# nrf_ha_sensor_Power_supply.net
KiCad netlist of a schematic drawn in Altium Designer
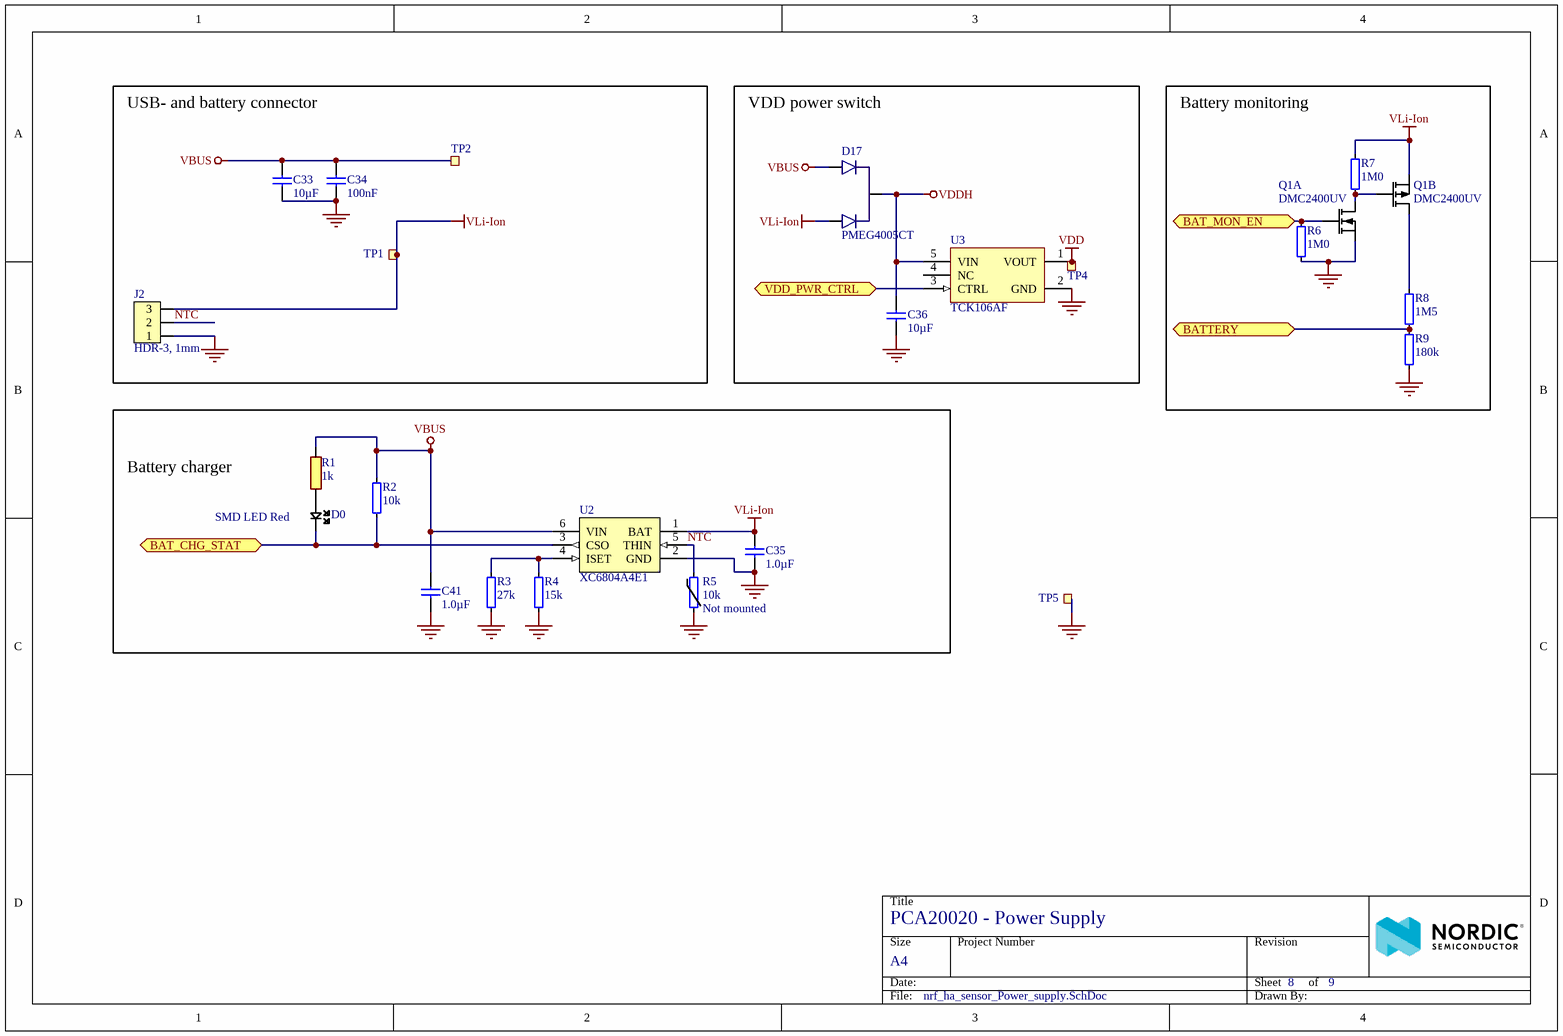
[diagram p0: nrf_ha_sensor_Power_supply.SchDoc]

(export (version "E")
  (design (tool "Eeschema 10.0.6"))
  (components
    (comp (ref "C33")
      (value "10µF")
      (footprint "CAPC1608X06L")
      (description "Capacitor, X5R, ±20%")
      (fields (field (name "PART NUMBER") "C0603-10µ") (field (name "PUBLISHER") "Nordic Semiconductor"))
      (libsource (lib "Nordic Passive DB") (part "CAP"))
    )
    (comp (ref "C34")
      (value "100nF")
      (footprint "CAPC1005X04L")
      (description "Capacitor, X7R, ±10%")
      (fields (field (name "PART NUMBER") "C0402-100n") (field (name "PUBLISHER") "Nordic Semiconductor"))
      (libsource (lib "Nordic Passive DB") (part "CAP"))
    )
    (comp (ref "C35")
      (value "1.0µF")
      (footprint "CAPC1608X06L")
      (description "Capacitor, X7R, ±10%")
      (fields (field (name "PART NUMBER") "C0603-1µ0") (field (name "PUBLISHER") "Nordic Semiconductor"))
      (libsource (lib "Nordic Passive DB") (part "CAP"))
    )
    (comp (ref "C36")
      (value "10µF")
      (footprint "CAPC1608X06L")
      (description "Capacitor, X5R, ±20%")
      (fields (field (name "PART NUMBER") "C0603-10µ") (field (name "PUBLISHER") "Nordic Semiconductor"))
      (libsource (lib "Nordic Passive DB") (part "CAP"))
    )
    (comp (ref "C41")
      (value "1.0µF")
      (footprint "CAPC1608X06L")
      (description "Capacitor, X7R, ±10%")
      (fields (field (name "PART NUMBER") "C0603-1µ0") (field (name "PUBLISHER") "Nordic Semiconductor"))
      (libsource (lib "Nordic Passive DB") (part "CAP"))
    )
    (comp (ref "D0")
      (value "SMD LED Red")
      (footprint "I_LEDC0603(1608)_N")
      (description "SMD")
      (libsource (lib "OVLib_64") (part "LED"))
    )
    (comp (ref "D17")
      (value "PMEG4005CT")
      (footprint "SOT95P230X110-3N")
      (libsource (lib "PMEG4005CT") (part "PMEG4005CT"))
    )
    (comp (ref "J2")
      (value "HDR-3, 1mm")
      (footprint "SM03B-SRSS-TB")
      (description "1.0mm pitch connector side entry SMD")
      (fields
        (field (name "PART NUMBER") "SM03B-SRSS-TB")
        (field (name "MANUFACTURER") "JST")
        (field (name "PUBLISHER") "Nordic Semiconductor")
      )
      (libsource (lib "Nordic Passive DB") (part "CONN-3"))
    )
    (comp (ref "Q1")
      (value "DMC2400UV")
      (footprint "SOTFL50P162X60-6N")
      (description "Dual N & P Ch MOFET, 1.03A/0.7A, 480mOhm, 450mW")
      (fields
        (field (name "MANUFACTURER") "Diodes Incorporated")
        (field (name "PUBLISHER") "Nordic Semiconductor")
      )
      (libsource (lib "Nordic Discrete DB") (part "T{colon}FET-N/P-DUAL"))
    )
    (comp (ref "R1")
      (value "1k")
      (footprint "RESC0603(1608)_N")
      (description "0.1W 1% Thick film resistor")
      (libsource (lib "OVLib_64") (part "Resistor2"))
    )
    (comp (ref "R2")
      (value "10k")
      (footprint "RESC1005X04L")
      (description "Resistor, ±1%, 0.063W")
      (fields (field (name "PART NUMBER") "R0402-10k") (field (name "PUBLISHER") "Nordic Semiconductor"))
      (libsource (lib "Nordic Passive DB") (part "RES_1"))
    )
    (comp (ref "R3")
      (value "27k")
      (footprint "RESC1005X04L")
      (description "Resistor, ±1%, 0.063W")
      (fields (field (name "PART NUMBER") "R0402-27k") (field (name "PUBLISHER") "Nordic Semiconductor"))
      (libsource (lib "Nordic Passive DB") (part "RES_1"))
    )
    (comp (ref "R4")
      (value "15k")
      (footprint "RESC1005X04L")
      (description "Resistor, ±1%, 0.063W")
      (fields (field (name "PART NUMBER") "R0402-15k") (field (name "PUBLISHER") "Nordic Semiconductor"))
      (libsource (lib "Nordic Passive DB") (part "RES_1"))
    )
    (comp (ref "R5")
      (value "10k")
      (footprint "RESC1005X04L")
      (description "THERMISTOR 10K OHM NTC 0402 SMD")
      (fields
        (field (name "PART NUMBER") "NCP15XH103F03RC")
        (field (name "MANUFACTURER") "Murata")
        (field (name "ASSEMBLY") "Not mounted")
        (field (name "PUBLISHER") "Nordic Semiconductor")
      )
      (libsource (lib "Nordic Passive DB") (part "RES_NTC"))
    )
    (comp (ref "R6")
      (value "1M0")
      (footprint "RESC1005X04L")
      (description "Resistor, ±1%, 0.063W")
      (fields (field (name "PART NUMBER") "R0402-1M0") (field (name "PUBLISHER") "Nordic Semiconductor"))
      (libsource (lib "Nordic Passive DB") (part "RES_1"))
    )
    (comp (ref "R7")
      (value "1M0")
      (footprint "RESC1005X04L")
      (description "Resistor, ±1%, 0.063W")
      (fields (field (name "PART NUMBER") "R0402-1M0") (field (name "PUBLISHER") "Nordic Semiconductor"))
      (libsource (lib "Nordic Passive DB") (part "RES_1"))
    )
    (comp (ref "R8")
      (value "1M5")
      (footprint "RESC1005X04L")
      (description "Resistor, ±1%, 0.063W")
      (fields (field (name "PART NUMBER") "R0402-1M5") (field (name "PUBLISHER") "Nordic Semiconductor"))
      (libsource (lib "Nordic Passive DB") (part "RES_1"))
    )
    (comp (ref "R9")
      (value "180k")
      (footprint "RESC1005X04L")
      (description "Resistor, ±1%, 0.063W")
      (fields (field (name "PART NUMBER") "R0402-180k") (field (name "PUBLISHER") "Nordic Semiconductor"))
      (libsource (lib "Nordic Passive DB") (part "RES_1"))
    )
    (comp (ref "TP1")
      (value "Ø1.5mm,SMD")
      (footprint "TP_SMD_Ø1.5mm")
      (description "1.0mm circular SMD testpad")
      (fields
        (field (name "PART NUMBER") "TP_SMD_Ø1.5MM")
        (field (name "MANUFACTURER") "Nordic Semiconductor")
        (field (name "PUBLISHER") "Nordic Semiconductor")
      )
      (libsource (lib "Nordic Passive DB") (part "TESTPAD"))
    )
    (comp (ref "TP2")
      (value "Ø1.5mm,SMD")
      (footprint "TP_SMD_Ø1.5mm")
      (description "1.0mm circular SMD testpad")
      (fields
        (field (name "PART NUMBER") "TP_SMD_Ø1.5MM")
        (field (name "MANUFACTURER") "Nordic Semiconductor")
        (field (name "PUBLISHER") "Nordic Semiconductor")
      )
      (libsource (lib "") (part "TESTPAD_2"))
    )
    (comp (ref "TP4")
      (value "Ø1.5mm,SMD")
      (footprint "TP_SMD_Ø1.5mm")
      (description "1.0mm circular SMD testpad")
      (fields
        (field (name "PART NUMBER") "TP_SMD_Ø1.5MM")
        (field (name "MANUFACTURER") "Nordic Semiconductor")
        (field (name "PUBLISHER") "Nordic Semiconductor")
      )
      (libsource (lib "") (part "TESTPAD_1"))
    )
    (comp (ref "TP5")
      (value "Ø1.5mm,SMD")
      (footprint "TP_SMD_Ø1.5mm")
      (description "1.0mm circular SMD testpad")
      (fields
        (field (name "PART NUMBER") "TP_SMD_Ø1.5MM")
        (field (name "MANUFACTURER") "Nordic Semiconductor")
        (field (name "PUBLISHER") "Nordic Semiconductor")
      )
      (libsource (lib "Nordic Passive DB") (part "TESTPAD"))
    )
    (comp (ref "U2")
      (value "XC6804A4E1")
      (footprint "USP-6EL")
      (description "One Cell Li-ion/Li-polymer Linear Charger IC with Battery Temperature Detection")
      (fields
        (field (name "PART NUMBER") "XC6804A4E14R-G")
        (field (name "MANUFACTURER") "Torex Semiconductor")
        (field (name "PUBLISHER") "Nordic Semiconductor")
      )
      (libsource (lib "Nordic Active DB") (part "XC6804"))
    )
    (comp (ref "U3")
      (value "TCK106AF")
      (footprint "SOT95P280X140-5N")
      (description "1.0 A Load Switch IC with Slew Rate Control Driver in Small Package")
      (fields
        (field (name "PART NUMBER") "TCK106AF,LF")
        (field (name "MANUFACTURER") "Toshiba")
        (field (name "PUBLISHER") "Nordic Semiconductor")
      )
      (libsource (lib "Nordic Active DB") (part "TCK10xAF"))
    )
  )
  (nets
    (net (code "1") (name "/BATTERY") (class "Default")
      (node (ref "R8") (pin "2") (pinfunction "2_2") (pintype "passive"))
      (node (ref "R9") (pin "1") (pinfunction "1_1") (pintype "passive"))
    )
    (net (code "2") (name "/BAT_CHG_STAT") (class "Default")
      (node (ref "D0") (pin "2") (pinfunction "2_2") (pintype "passive"))
      (node (ref "R2") (pin "2") (pinfunction "2_2") (pintype "passive"))
      (node (ref "U2") (pin "3") (pinfunction "CSO_3") (pintype "output"))
    )
    (net (code "3") (name "/BAT_MON_EN") (class "Default")
      (node (ref "Q1") (pin "2") (pinfunction "G1_2") (pintype "passive"))
      (node (ref "R6") (pin "1") (pinfunction "1_1") (pintype "passive"))
    )
    (net (code "4") (name "/NTC") (class "Default")
      (node (ref "J2") (pin "2") (pinfunction "2_2") (pintype "passive"))
      (node (ref "R5") (pin "1") (pinfunction "1_1") (pintype "passive"))
      (node (ref "U2") (pin "5") (pinfunction "THIN_5") (pintype "input"))
    )
    (net (code "5") (name "/VDD_PWR_CTRL") (class "Default")
      (node (ref "U3") (pin "3") (pinfunction "CTRL_3") (pintype "input"))
    )
    (net (code "6") (name "GND") (class "Default")
      (node (ref "C33") (pin "2") (pinfunction "2_2") (pintype "passive"))
      (node (ref "C34") (pin "2") (pinfunction "2_2") (pintype "passive"))
      (node (ref "C35") (pin "1") (pinfunction "1_1") (pintype "passive"))
      (node (ref "C36") (pin "1") (pinfunction "1_1") (pintype "passive"))
      (node (ref "C41") (pin "1") (pinfunction "1_1") (pintype "passive"))
      (node (ref "J2") (pin "1") (pinfunction "1_1") (pintype "passive"))
      (node (ref "Q1") (pin "1") (pinfunction "S1_1") (pintype "passive"))
      (node (ref "R3") (pin "2") (pinfunction "2_2") (pintype "passive"))
      (node (ref "R4") (pin "2") (pinfunction "2_2") (pintype "passive"))
      (node (ref "R5") (pin "2") (pinfunction "2_2") (pintype "passive"))
      (node (ref "R6") (pin "2") (pinfunction "2_2") (pintype "passive"))
      (node (ref "R9") (pin "2") (pinfunction "2_2") (pintype "passive"))
      (node (ref "TP5") (pin "1") (pinfunction "1_1") (pintype "passive"))
      (node (ref "U2") (pin "2") (pinfunction "GND_2") (pintype "power_in"))
      (node (ref "U2") (pin "7") (pinfunction "GND_7") (pintype "power_in"))
      (node (ref "U3") (pin "2") (pinfunction "GND_2") (pintype "power_in"))
    )
    (net (code "7") (name "Net-(D0-Pad1)") (class "Default")
      (node (ref "D0") (pin "1") (pinfunction "1_1") (pintype "passive"))
      (node (ref "R1") (pin "1") (pinfunction "1_1") (pintype "passive"))
    )
    (net (code "8") (name "Net-(Q1A-D1)") (class "Default")
      (node (ref "Q1") (pin "5") (pinfunction "G2_5") (pintype "passive"))
      (node (ref "Q1") (pin "6") (pinfunction "D1_6") (pintype "passive"))
      (node (ref "R7") (pin "2") (pinfunction "2_2") (pintype "passive"))
    )
    (net (code "9") (name "Net-(Q1B-D2)") (class "Default")
      (node (ref "Q1") (pin "3") (pinfunction "D2_3") (pintype "passive"))
      (node (ref "R8") (pin "1") (pinfunction "1_1") (pintype "passive"))
    )
    (net (code "10") (name "Net-(U2-ISET)") (class "Default")
      (node (ref "R3") (pin "1") (pinfunction "1_1") (pintype "passive"))
      (node (ref "R4") (pin "1") (pinfunction "1_1") (pintype "passive"))
      (node (ref "U2") (pin "4") (pinfunction "ISET_4") (pintype "input"))
    )
    (net (code "11") (name "VBUS") (class "Default")
      (node (ref "C33") (pin "1") (pinfunction "1_1") (pintype "passive"))
      (node (ref "C34") (pin "1") (pinfunction "1_1") (pintype "passive"))
      (node (ref "C41") (pin "2") (pinfunction "2_2") (pintype "passive"))
      (node (ref "D17") (pin "2") (pinfunction "A_2") (pintype "passive"))
      (node (ref "R1") (pin "2") (pinfunction "2_2") (pintype "passive"))
      (node (ref "R2") (pin "1") (pinfunction "1_1") (pintype "passive"))
      (node (ref "TP2") (pin "1") (pinfunction "1_1") (pintype "passive"))
      (node (ref "U2") (pin "6") (pinfunction "VIN_6") (pintype "power_in"))
    )
    (net (code "12") (name "VDD") (class "Default")
      (node (ref "TP4") (pin "1") (pinfunction "1_1") (pintype "passive"))
      (node (ref "U3") (pin "1") (pinfunction "VOUT_1") (pintype "power_in"))
    )
    (net (code "13") (name "VDDH") (class "Default")
      (node (ref "C36") (pin "2") (pinfunction "2_2") (pintype "passive"))
      (node (ref "D17") (pin "3") (pinfunction "C_3") (pintype "passive"))
      (node (ref "U3") (pin "5") (pinfunction "VIN_5") (pintype "power_in"))
    )
    (net (code "14") (name "VLi-Ion") (class "Default")
      (node (ref "C35") (pin "2") (pinfunction "2_2") (pintype "passive"))
      (node (ref "D17") (pin "1") (pinfunction "A_1") (pintype "passive"))
      (node (ref "J2") (pin "3") (pinfunction "3_3") (pintype "passive"))
      (node (ref "Q1") (pin "4") (pinfunction "S2_4") (pintype "passive"))
      (node (ref "R7") (pin "1") (pinfunction "1_1") (pintype "passive"))
      (node (ref "TP1") (pin "1") (pinfunction "1_1") (pintype "passive"))
      (node (ref "U2") (pin "1") (pinfunction "BAT_1") (pintype "power_in"))
    )
    (net (code "15") (name "unconnected-(U3-NC-Pad4)") (class "Default")
      (node (ref "U3") (pin "4") (pinfunction "NC_4") (pintype "passive"))
    )
  )
)
